# power_ldo.net
KiCad netlist of a schematic drawn in EAGLE
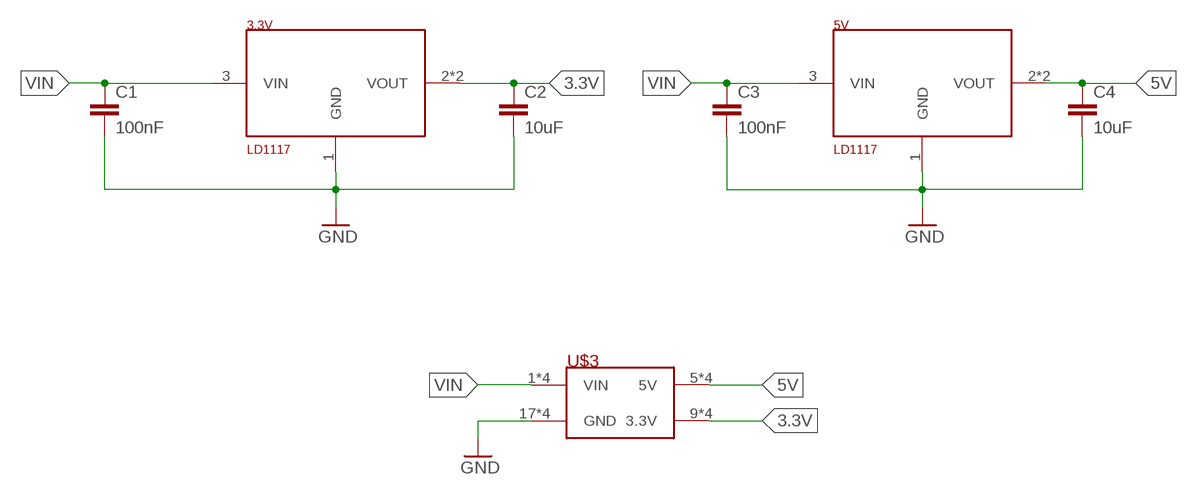
[diagram p0: schematic, sheet 1]

(export (version "E")
  (design (tool "Eeschema 10.0.6"))
  (components
    (comp (ref "3.3V")
      (value "LD1117\"")
      (footprint "eagle-import:SOT223")
      (libsource (lib "eagle-import") (part "LD1117{dblquote}"))
    )
    (comp (ref "5V")
      (value "LD1117\"")
      (footprint "eagle-import:SOT223")
      (libsource (lib "eagle-import") (part "LD1117{dblquote}"))
    )
    (comp (ref "C1")
      (value "100nF")
      (footprint "eagle-import:C0603")
      (libsource (lib "eagle-import") (part "C-EUC0603"))
    )
    (comp (ref "C2")
      (value "10uF")
      (footprint "eagle-import:C0603")
      (libsource (lib "eagle-import") (part "C-EUC0603"))
    )
    (comp (ref "C3")
      (value "100nF")
      (footprint "eagle-import:C0603")
      (libsource (lib "eagle-import") (part "C-EUC0603"))
    )
    (comp (ref "C4")
      (value "10uF")
      (footprint "eagle-import:C0603")
      (libsource (lib "eagle-import") (part "C-EUC0603"))
    )
    (comp (ref "U$3")
      (value "POWER_EDGE_CONNEDGE")
      (footprint "eagle-import:20-PIN-CARD-EDGE")
      (libsource (lib "eagle-import") (part "POWER_EDGE_CONNEDGE"))
    )
  )
  (nets
    (net (code "1") (name "3.3V") (class "Default")
      (node (ref "3.3V") (pin "2") (pinfunction "VOUT_2") (pintype "bidirectional"))
      (node (ref "3.3V") (pin "4") (pinfunction "VOUT_4") (pintype "bidirectional"))
      (node (ref "C2") (pin "1") (pinfunction "1_1") (pintype "passive"))
      (node (ref "U$3") (pin "10") (pinfunction "3.3V_10") (pintype "bidirectional"))
      (node (ref "U$3") (pin "11") (pinfunction "3.3V_11") (pintype "bidirectional"))
      (node (ref "U$3") (pin "12") (pinfunction "3.3V_12") (pintype "bidirectional"))
      (node (ref "U$3") (pin "9") (pinfunction "3.3V_9") (pintype "bidirectional"))
    )
    (net (code "2") (name "5V") (class "Default")
      (node (ref "5V") (pin "2") (pinfunction "VOUT_2") (pintype "bidirectional"))
      (node (ref "5V") (pin "4") (pinfunction "VOUT_4") (pintype "bidirectional"))
      (node (ref "C4") (pin "1") (pinfunction "1_1") (pintype "passive"))
      (node (ref "U$3") (pin "5") (pinfunction "5V_5") (pintype "bidirectional"))
      (node (ref "U$3") (pin "6") (pinfunction "5V_6") (pintype "bidirectional"))
      (node (ref "U$3") (pin "7") (pinfunction "5V_7") (pintype "bidirectional"))
      (node (ref "U$3") (pin "8") (pinfunction "5V_8") (pintype "bidirectional"))
    )
    (net (code "3") (name "GND") (class "Default")
      (node (ref "3.3V") (pin "1") (pinfunction "GND_1") (pintype "bidirectional"))
      (node (ref "5V") (pin "1") (pinfunction "GND_1") (pintype "bidirectional"))
      (node (ref "C1") (pin "2") (pinfunction "2_2") (pintype "passive"))
      (node (ref "C2") (pin "2") (pinfunction "2_2") (pintype "passive"))
      (node (ref "C3") (pin "2") (pinfunction "2_2") (pintype "passive"))
      (node (ref "C4") (pin "2") (pinfunction "2_2") (pintype "passive"))
      (node (ref "U$3") (pin "17") (pinfunction "GND_17") (pintype "bidirectional"))
      (node (ref "U$3") (pin "18") (pinfunction "GND_18") (pintype "bidirectional"))
      (node (ref "U$3") (pin "19") (pinfunction "GND_19") (pintype "bidirectional"))
      (node (ref "U$3") (pin "20") (pinfunction "GND_20") (pintype "bidirectional"))
    )
    (net (code "4") (name "VIN") (class "Default")
      (node (ref "3.3V") (pin "3") (pinfunction "VIN_3") (pintype "bidirectional"))
      (node (ref "5V") (pin "3") (pinfunction "VIN_3") (pintype "bidirectional"))
      (node (ref "C1") (pin "1") (pinfunction "1_1") (pintype "passive"))
      (node (ref "C3") (pin "1") (pinfunction "1_1") (pintype "passive"))
      (node (ref "U$3") (pin "1") (pinfunction "VIN_1") (pintype "bidirectional"))
      (node (ref "U$3") (pin "2") (pinfunction "VIN_2") (pintype "bidirectional"))
      (node (ref "U$3") (pin "3") (pinfunction "VIN_3") (pintype "bidirectional"))
      (node (ref "U$3") (pin "4") (pinfunction "VIN_4") (pintype "bidirectional"))
    )
  )
)
